# max31855.net
KiCad netlist of a schematic drawn in EAGLE
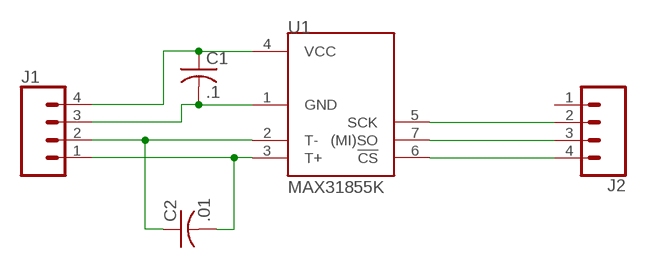
[diagram p0: schematic, sheet 1]

(export (version "E")
  (design (tool "Eeschema 10.0.6"))
  (components
    (comp (ref "C1")
      (value ".1")
      (footprint "eagle-import:C0805")
      (libsource (lib "eagle-import") (part "C-USC0805"))
    )
    (comp (ref "C2")
      (value ".01")
      (footprint "eagle-import:C0805")
      (libsource (lib "eagle-import") (part "C-USC0805"))
    )
    (comp (ref "J1")
      (value "CONN_04")
      (footprint "eagle-import:1X04")
      (libsource (lib "eagle-import") (part "CONN_04"))
    )
    (comp (ref "J2")
      (value "CONN_04")
      (footprint "eagle-import:1X04")
      (libsource (lib "eagle-import") (part "CONN_04"))
    )
    (comp (ref "U1")
      (value "MAX31855K")
      (footprint "eagle-import:SO08")
      (libsource (lib "eagle-import") (part "MAX31855K"))
    )
  )
  (nets
    (net (code "1") (name "Net-(U1-(MI)SO)") (class "Default")
      (node (ref "J2") (pin "3") (pinfunction "3_3") (pintype "passive"))
      (node (ref "U1") (pin "7") (pinfunction "(MI)SO_7") (pintype "bidirectional"))
    )
    (net (code "2") (name "Net-(U1-GND)") (class "Default")
      (node (ref "C1") (pin "2") (pinfunction "2_2") (pintype "passive"))
      (node (ref "J1") (pin "3") (pinfunction "3_3") (pintype "passive"))
      (node (ref "U1") (pin "1") (pinfunction "GND_1") (pintype "bidirectional"))
    )
    (net (code "3") (name "Net-(U1-SCK)") (class "Default")
      (node (ref "J2") (pin "2") (pinfunction "2_2") (pintype "passive"))
      (node (ref "U1") (pin "5") (pinfunction "SCK_5") (pintype "bidirectional"))
    )
    (net (code "4") (name "Net-(U1-T+)") (class "Default")
      (node (ref "C2") (pin "2") (pinfunction "2_2") (pintype "passive"))
      (node (ref "J1") (pin "1") (pinfunction "1_1") (pintype "passive"))
      (node (ref "U1") (pin "3") (pinfunction "T+_3") (pintype "bidirectional"))
    )
    (net (code "5") (name "Net-(U1-T-)") (class "Default")
      (node (ref "C2") (pin "1") (pinfunction "1_1") (pintype "passive"))
      (node (ref "J1") (pin "2") (pinfunction "2_2") (pintype "passive"))
      (node (ref "U1") (pin "2") (pinfunction "T-_2") (pintype "bidirectional"))
    )
    (net (code "6") (name "Net-(U1-VCC)") (class "Default")
      (node (ref "C1") (pin "1") (pinfunction "1_1") (pintype "passive"))
      (node (ref "J1") (pin "4") (pinfunction "4_4") (pintype "passive"))
      (node (ref "U1") (pin "4") (pinfunction "VCC_4") (pintype "bidirectional"))
    )
    (net (code "7") (name "Net-(U1-~{CS})") (class "Default")
      (node (ref "J2") (pin "4") (pinfunction "4_4") (pintype "passive"))
      (node (ref "U1") (pin "6") (pinfunction "~{CS}_6") (pintype "bidirectional"))
    )
    (net (code "8") (name "unconnected-(J2-Pad1)") (class "Default")
      (node (ref "J2") (pin "1") (pinfunction "1_1") (pintype "passive"))
    )
  )
)
